# SCH_Minotaur_Remote_Controller_2024-04-1.net
KiCad netlist of a schematic drawn in EasyEDA
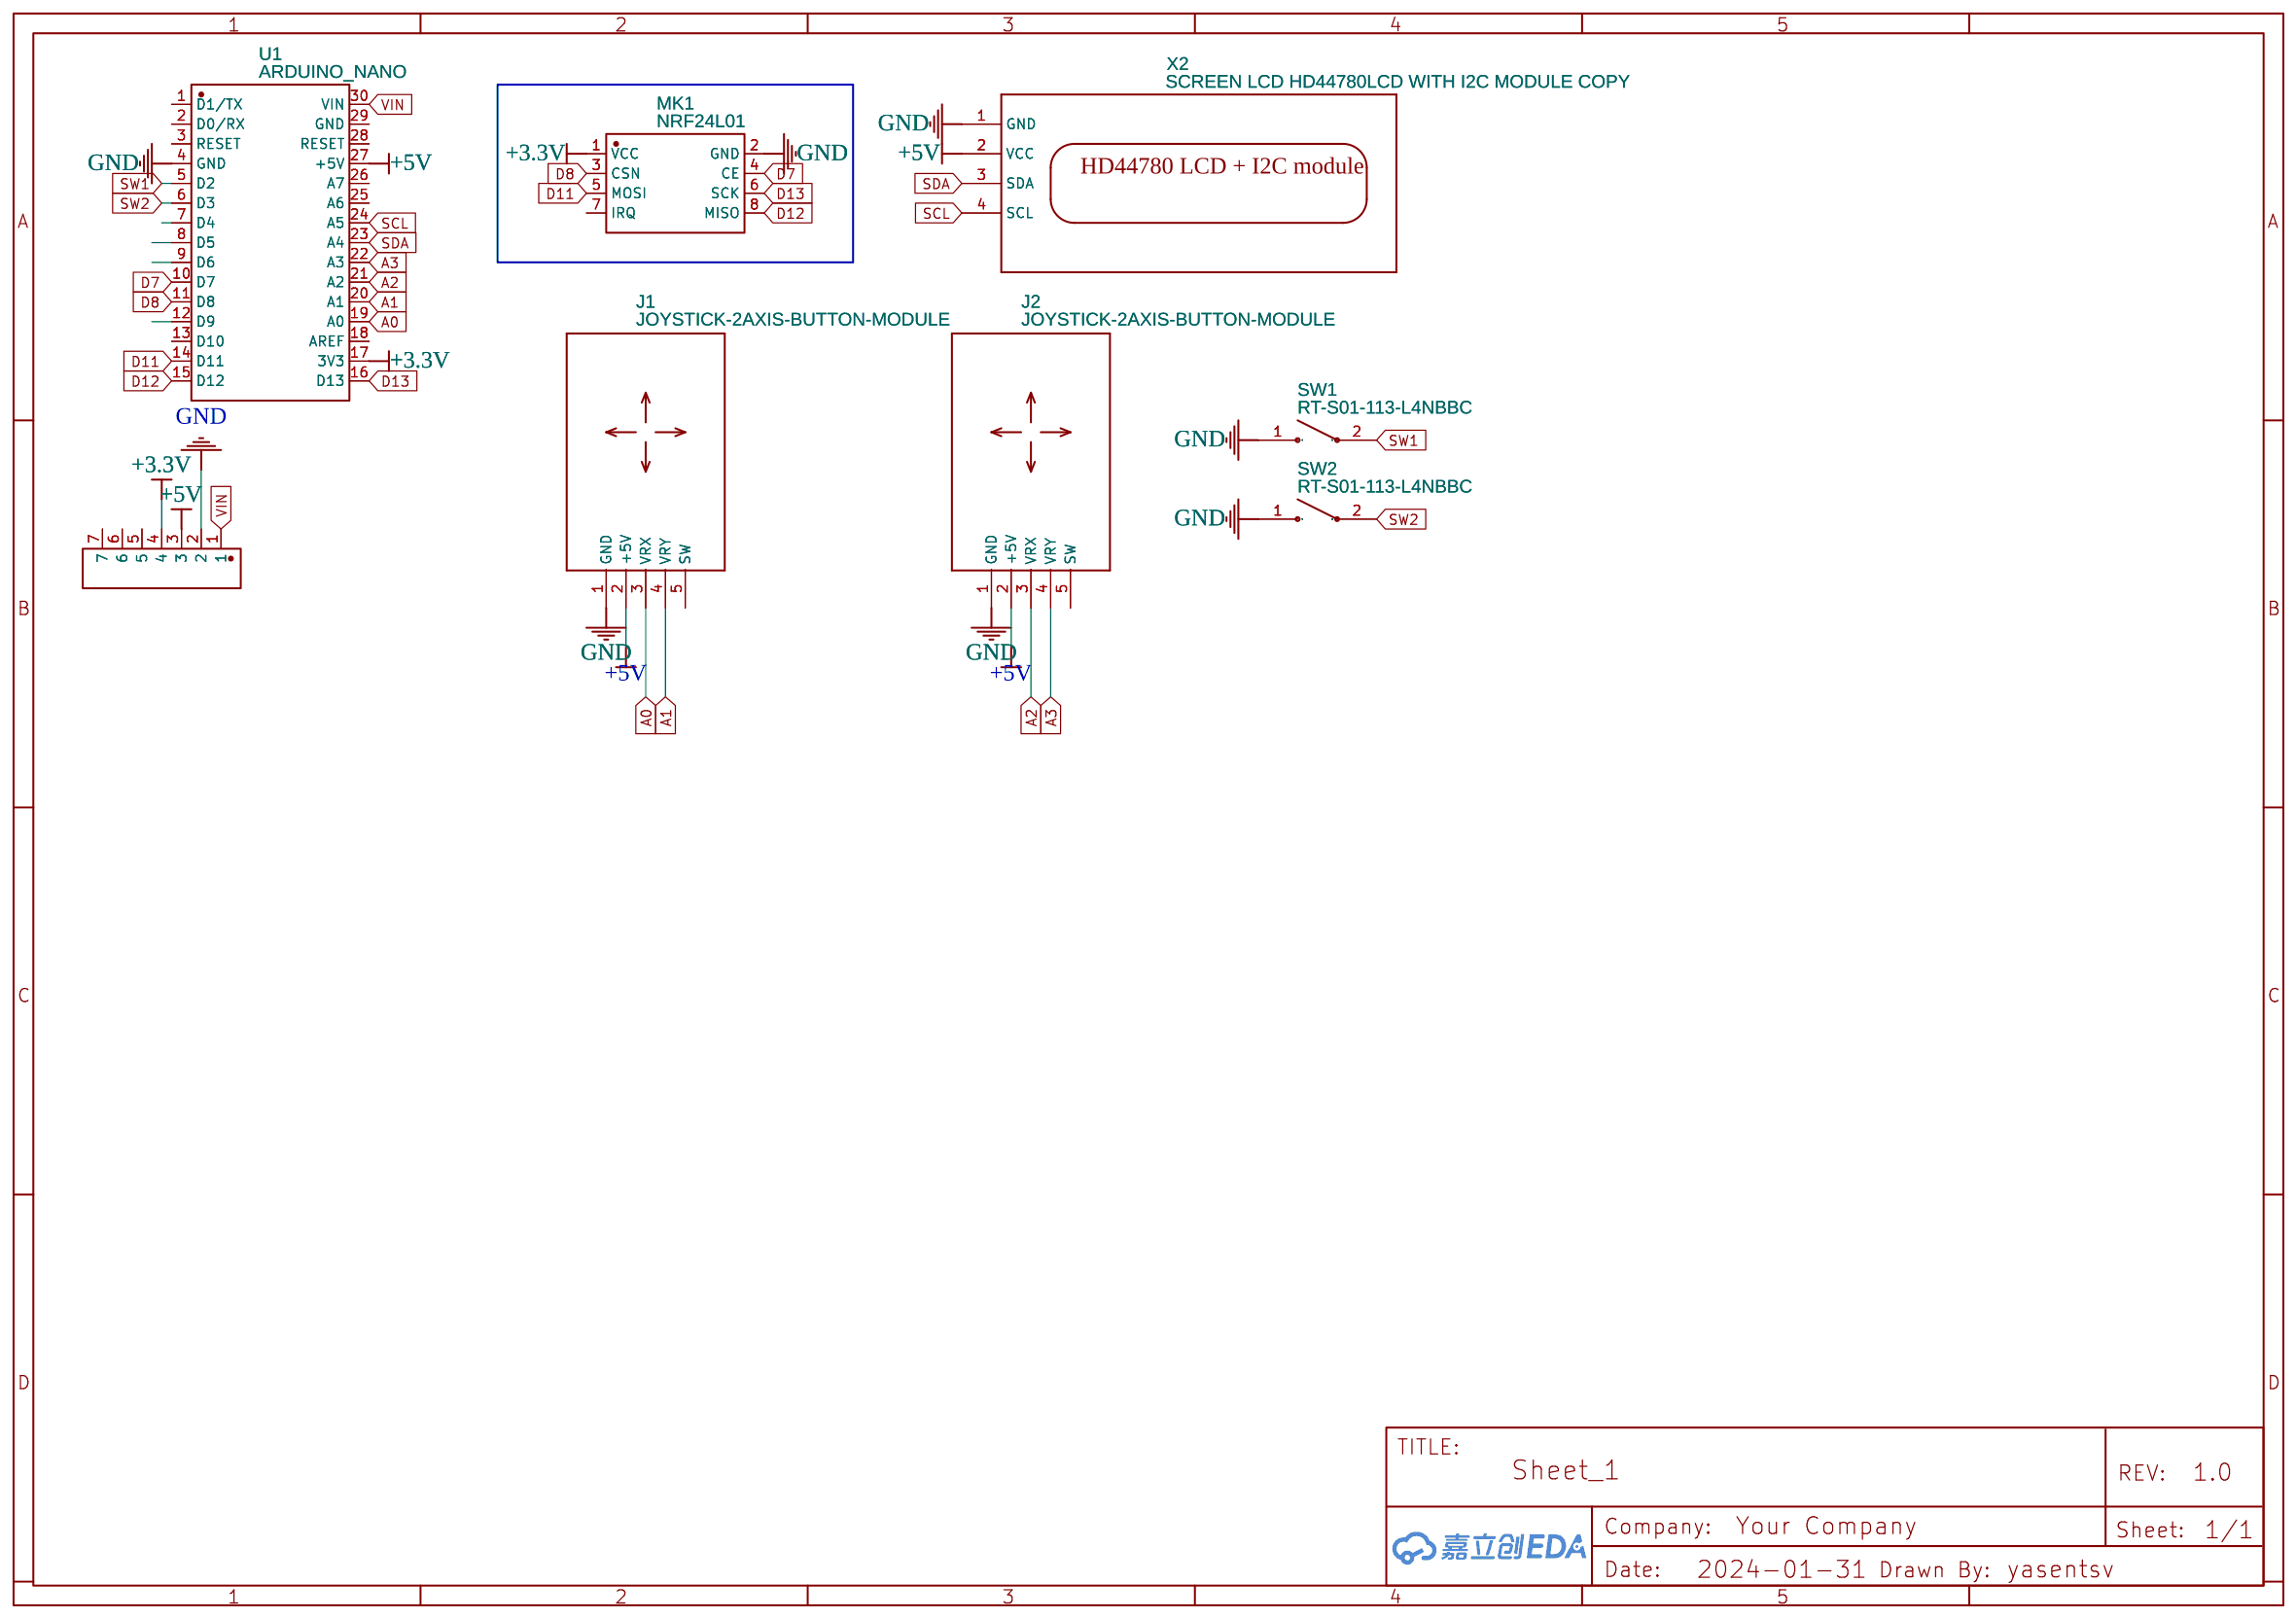
[diagram p0: schematic sheet]

(export (version "E")
  (design (tool "Eeschema 10.0.6"))
  (components
    (comp (ref "J1")
      (value "JOYSTICK-2AXIS-BUTTON-MODULE")
      (libsource (lib "") (part "JOYSTICK-2AXIS-BUTTON-MODULE"))
    )
    (comp (ref "J2")
      (value "JOYSTICK-2AXIS-BUTTON-MODULE")
      (libsource (lib "") (part "JOYSTICK-2AXIS-BUTTON-MODULE"))
    )
    (comp (ref "MK1")
      (value "NRF24L01")
      (fields (field (name "Manufacturer") "Ai-Thinker(安信可)"))
      (libsource (lib "") (part "NRF24L01"))
    )
    (comp (ref "SW1")
      (value "RT-S01-113-L4NBBC")
      (fields (field (name "Manufacturer") "ROCKTEK(富力隆)"))
      (libsource (lib "") (part "RT-S01-113-L4NBBC"))
    )
    (comp (ref "SW2")
      (value "RT-S01-113-L4NBBC")
      (fields (field (name "Manufacturer") "ROCKTEK(富力隆)"))
      (libsource (lib "") (part "RT-S01-113-L4NBBC"))
    )
    (comp (ref "U1") (value "ARDUINO_NANO") (libsource (lib "") (part "ARDUINO_NANO")))
    (comp (ref "U4")
      (value "2.54MM双塑胶单排直针,总长17MM")
      (fields (field (name "Manufacturer Part") "2.54mm双塑胶单排直针,总长17mm"))
      (libsource (lib "") (part "2.54MM双塑胶单排直针,总长17MM"))
    )
    (comp (ref "X2")
      (value "SCREEN LCD HD44780LCD WITH I2C MODULE COPY")
      (libsource (lib "") (part "SCREEN LCD HD44780LCD WITH I2C MODULE COPY"))
    )
  )
  (nets
    (net (code "1") (name "+3.3V") (class "Default")
      (node (ref "MK1") (pin "1") (pinfunction "VCC_1") (pintype "unspecified"))
      (node (ref "U1") (pin "17") (pinfunction "3V3_17") (pintype "unspecified"))
      (node (ref "U4") (pin "4") (pinfunction "4_4") (pintype "unspecified"))
    )
    (net (code "2") (name "+5V") (class "Default")
      (node (ref "J1") (pin "2") (pinfunction "+5V_2") (pintype "bidirectional"))
      (node (ref "J2") (pin "2") (pinfunction "+5V_2") (pintype "bidirectional"))
      (node (ref "U1") (pin "27") (pinfunction "+5V_27") (pintype "unspecified"))
      (node (ref "U4") (pin "3") (pinfunction "3_3") (pintype "unspecified"))
      (node (ref "X2") (pin "2") (pinfunction "VCC_2") (pintype "unspecified"))
    )
    (net (code "3") (name "A0") (class "Default")
      (node (ref "J1") (pin "3") (pinfunction "VRX_3") (pintype "bidirectional"))
      (node (ref "U1") (pin "19") (pinfunction "A0_19") (pintype "unspecified"))
    )
    (net (code "4") (name "A1") (class "Default")
      (node (ref "J1") (pin "4") (pinfunction "VRY_4") (pintype "bidirectional"))
      (node (ref "U1") (pin "20") (pinfunction "A1_20") (pintype "unspecified"))
    )
    (net (code "5") (name "A2") (class "Default")
      (node (ref "J2") (pin "3") (pinfunction "VRX_3") (pintype "bidirectional"))
      (node (ref "U1") (pin "21") (pinfunction "A2_21") (pintype "unspecified"))
    )
    (net (code "6") (name "A3") (class "Default")
      (node (ref "J2") (pin "4") (pinfunction "VRY_4") (pintype "bidirectional"))
      (node (ref "U1") (pin "22") (pinfunction "A3_22") (pintype "unspecified"))
    )
    (net (code "7") (name "D7") (class "Default")
      (node (ref "MK1") (pin "4") (pinfunction "CE_4") (pintype "unspecified"))
      (node (ref "U1") (pin "10") (pinfunction "D7_10") (pintype "unspecified"))
    )
    (net (code "8") (name "D8") (class "Default")
      (node (ref "MK1") (pin "3") (pinfunction "CSN_3") (pintype "unspecified"))
      (node (ref "U1") (pin "11") (pinfunction "D8_11") (pintype "unspecified"))
    )
    (net (code "9") (name "D11") (class "Default")
      (node (ref "MK1") (pin "5") (pinfunction "MOSI_5") (pintype "unspecified"))
      (node (ref "U1") (pin "14") (pinfunction "D11_14") (pintype "unspecified"))
    )
    (net (code "10") (name "D12") (class "Default")
      (node (ref "MK1") (pin "8") (pinfunction "MISO_8") (pintype "unspecified"))
      (node (ref "U1") (pin "15") (pinfunction "D12_15") (pintype "unspecified"))
    )
    (net (code "11") (name "D13") (class "Default")
      (node (ref "MK1") (pin "6") (pinfunction "SCK_6") (pintype "unspecified"))
      (node (ref "U1") (pin "16") (pinfunction "D13_16") (pintype "unspecified"))
    )
    (net (code "12") (name "GND") (class "Default")
      (node (ref "J1") (pin "1") (pinfunction "GND_1") (pintype "bidirectional"))
      (node (ref "J2") (pin "1") (pinfunction "GND_1") (pintype "bidirectional"))
      (node (ref "MK1") (pin "2") (pinfunction "GND_2") (pintype "unspecified"))
      (node (ref "SW1") (pin "1") (pinfunction "1_1") (pintype "unspecified"))
      (node (ref "SW2") (pin "1") (pinfunction "1_1") (pintype "unspecified"))
      (node (ref "U1") (pin "4") (pinfunction "GND_4") (pintype "unspecified"))
      (node (ref "U4") (pin "2") (pinfunction "2_2") (pintype "unspecified"))
      (node (ref "X2") (pin "1") (pinfunction "GND_1") (pintype "unspecified"))
    )
    (net (code "13") (name "SCL") (class "Default")
      (node (ref "U1") (pin "24") (pinfunction "A5_24") (pintype "unspecified"))
      (node (ref "X2") (pin "4") (pinfunction "SCL_4") (pintype "unspecified"))
    )
    (net (code "14") (name "SDA") (class "Default")
      (node (ref "U1") (pin "23") (pinfunction "A4_23") (pintype "unspecified"))
      (node (ref "X2") (pin "3") (pinfunction "SDA_3") (pintype "unspecified"))
    )
    (net (code "15") (name "SW1") (class "Default")
      (node (ref "SW1") (pin "2") (pinfunction "2_2") (pintype "unspecified"))
      (node (ref "U1") (pin "5") (pinfunction "D2_5") (pintype "unspecified"))
    )
    (net (code "16") (name "SW2") (class "Default")
      (node (ref "SW2") (pin "2") (pinfunction "2_2") (pintype "unspecified"))
      (node (ref "U1") (pin "6") (pinfunction "D3_6") (pintype "unspecified"))
    )
    (net (code "17") (name "VIN") (class "Default")
      (node (ref "U1") (pin "30") (pinfunction "VIN_30") (pintype "unspecified"))
      (node (ref "U4") (pin "1") (pinfunction "1_1") (pintype "unspecified"))
    )
    (net (code "18") (name "unconnected-(J1-SW-Pad5)") (class "Default")
      (node (ref "J1") (pin "5") (pinfunction "SW_5") (pintype "bidirectional"))
    )
    (net (code "19") (name "unconnected-(J2-SW-Pad5)") (class "Default")
      (node (ref "J2") (pin "5") (pinfunction "SW_5") (pintype "bidirectional"))
    )
    (net (code "20") (name "unconnected-(MK1-IRQ-Pad7)") (class "Default")
      (node (ref "MK1") (pin "7") (pinfunction "IRQ_7") (pintype "unspecified"))
    )
    (net (code "21") (name "unconnected-(U1-A6-Pad25)") (class "Default")
      (node (ref "U1") (pin "25") (pinfunction "A6_25") (pintype "unspecified"))
    )
    (net (code "22") (name "unconnected-(U1-A7-Pad26)") (class "Default")
      (node (ref "U1") (pin "26") (pinfunction "A7_26") (pintype "unspecified"))
    )
    (net (code "23") (name "unconnected-(U1-AREF-Pad18)") (class "Default")
      (node (ref "U1") (pin "18") (pinfunction "AREF_18") (pintype "unspecified"))
    )
    (net (code "24") (name "unconnected-(U1-D0{slash}RX-Pad2)") (class "Default")
      (node (ref "U1") (pin "2") (pinfunction "D0/RX_2") (pintype "unspecified"))
    )
    (net (code "25") (name "unconnected-(U1-D1{slash}TX-Pad1)") (class "Default")
      (node (ref "U1") (pin "1") (pinfunction "D1/TX_1") (pintype "unspecified"))
    )
    (net (code "26") (name "unconnected-(U1-D4-Pad7)") (class "Default")
      (node (ref "U1") (pin "7") (pinfunction "D4_7") (pintype "unspecified"))
    )
    (net (code "27") (name "unconnected-(U1-D5-Pad8)") (class "Default")
      (node (ref "U1") (pin "8") (pinfunction "D5_8") (pintype "unspecified"))
    )
    (net (code "28") (name "unconnected-(U1-D6-Pad9)") (class "Default")
      (node (ref "U1") (pin "9") (pinfunction "D6_9") (pintype "unspecified"))
    )
    (net (code "29") (name "unconnected-(U1-D9-Pad12)") (class "Default")
      (node (ref "U1") (pin "12") (pinfunction "D9_12") (pintype "unspecified"))
    )
    (net (code "30") (name "unconnected-(U1-D10-Pad13)") (class "Default")
      (node (ref "U1") (pin "13") (pinfunction "D10_13") (pintype "unspecified"))
    )
    (net (code "31") (name "unconnected-(U1-GND-Pad29)") (class "Default")
      (node (ref "U1") (pin "29") (pinfunction "GND_29") (pintype "unspecified"))
    )
    (net (code "32") (name "unconnected-(U1-RESET-Pad3)") (class "Default")
      (node (ref "U1") (pin "3") (pinfunction "RESET_3") (pintype "unspecified"))
    )
    (net (code "33") (name "unconnected-(U1-RESET-Pad28)") (class "Default")
      (node (ref "U1") (pin "28") (pinfunction "RESET_28") (pintype "unspecified"))
    )
    (net (code "34") (name "unconnected-(U4-Pad5)") (class "Default")
      (node (ref "U4") (pin "5") (pinfunction "5_5") (pintype "unspecified"))
    )
    (net (code "35") (name "unconnected-(U4-Pad6)") (class "Default")
      (node (ref "U4") (pin "6") (pinfunction "6_6") (pintype "unspecified"))
    )
    (net (code "36") (name "unconnected-(U4-Pad7)") (class "Default")
      (node (ref "U4") (pin "7") (pinfunction "7_7") (pintype "unspecified"))
    )
  )
)
